# darwin-integrated.net
KiCad netlist of a schematic drawn in EAGLE
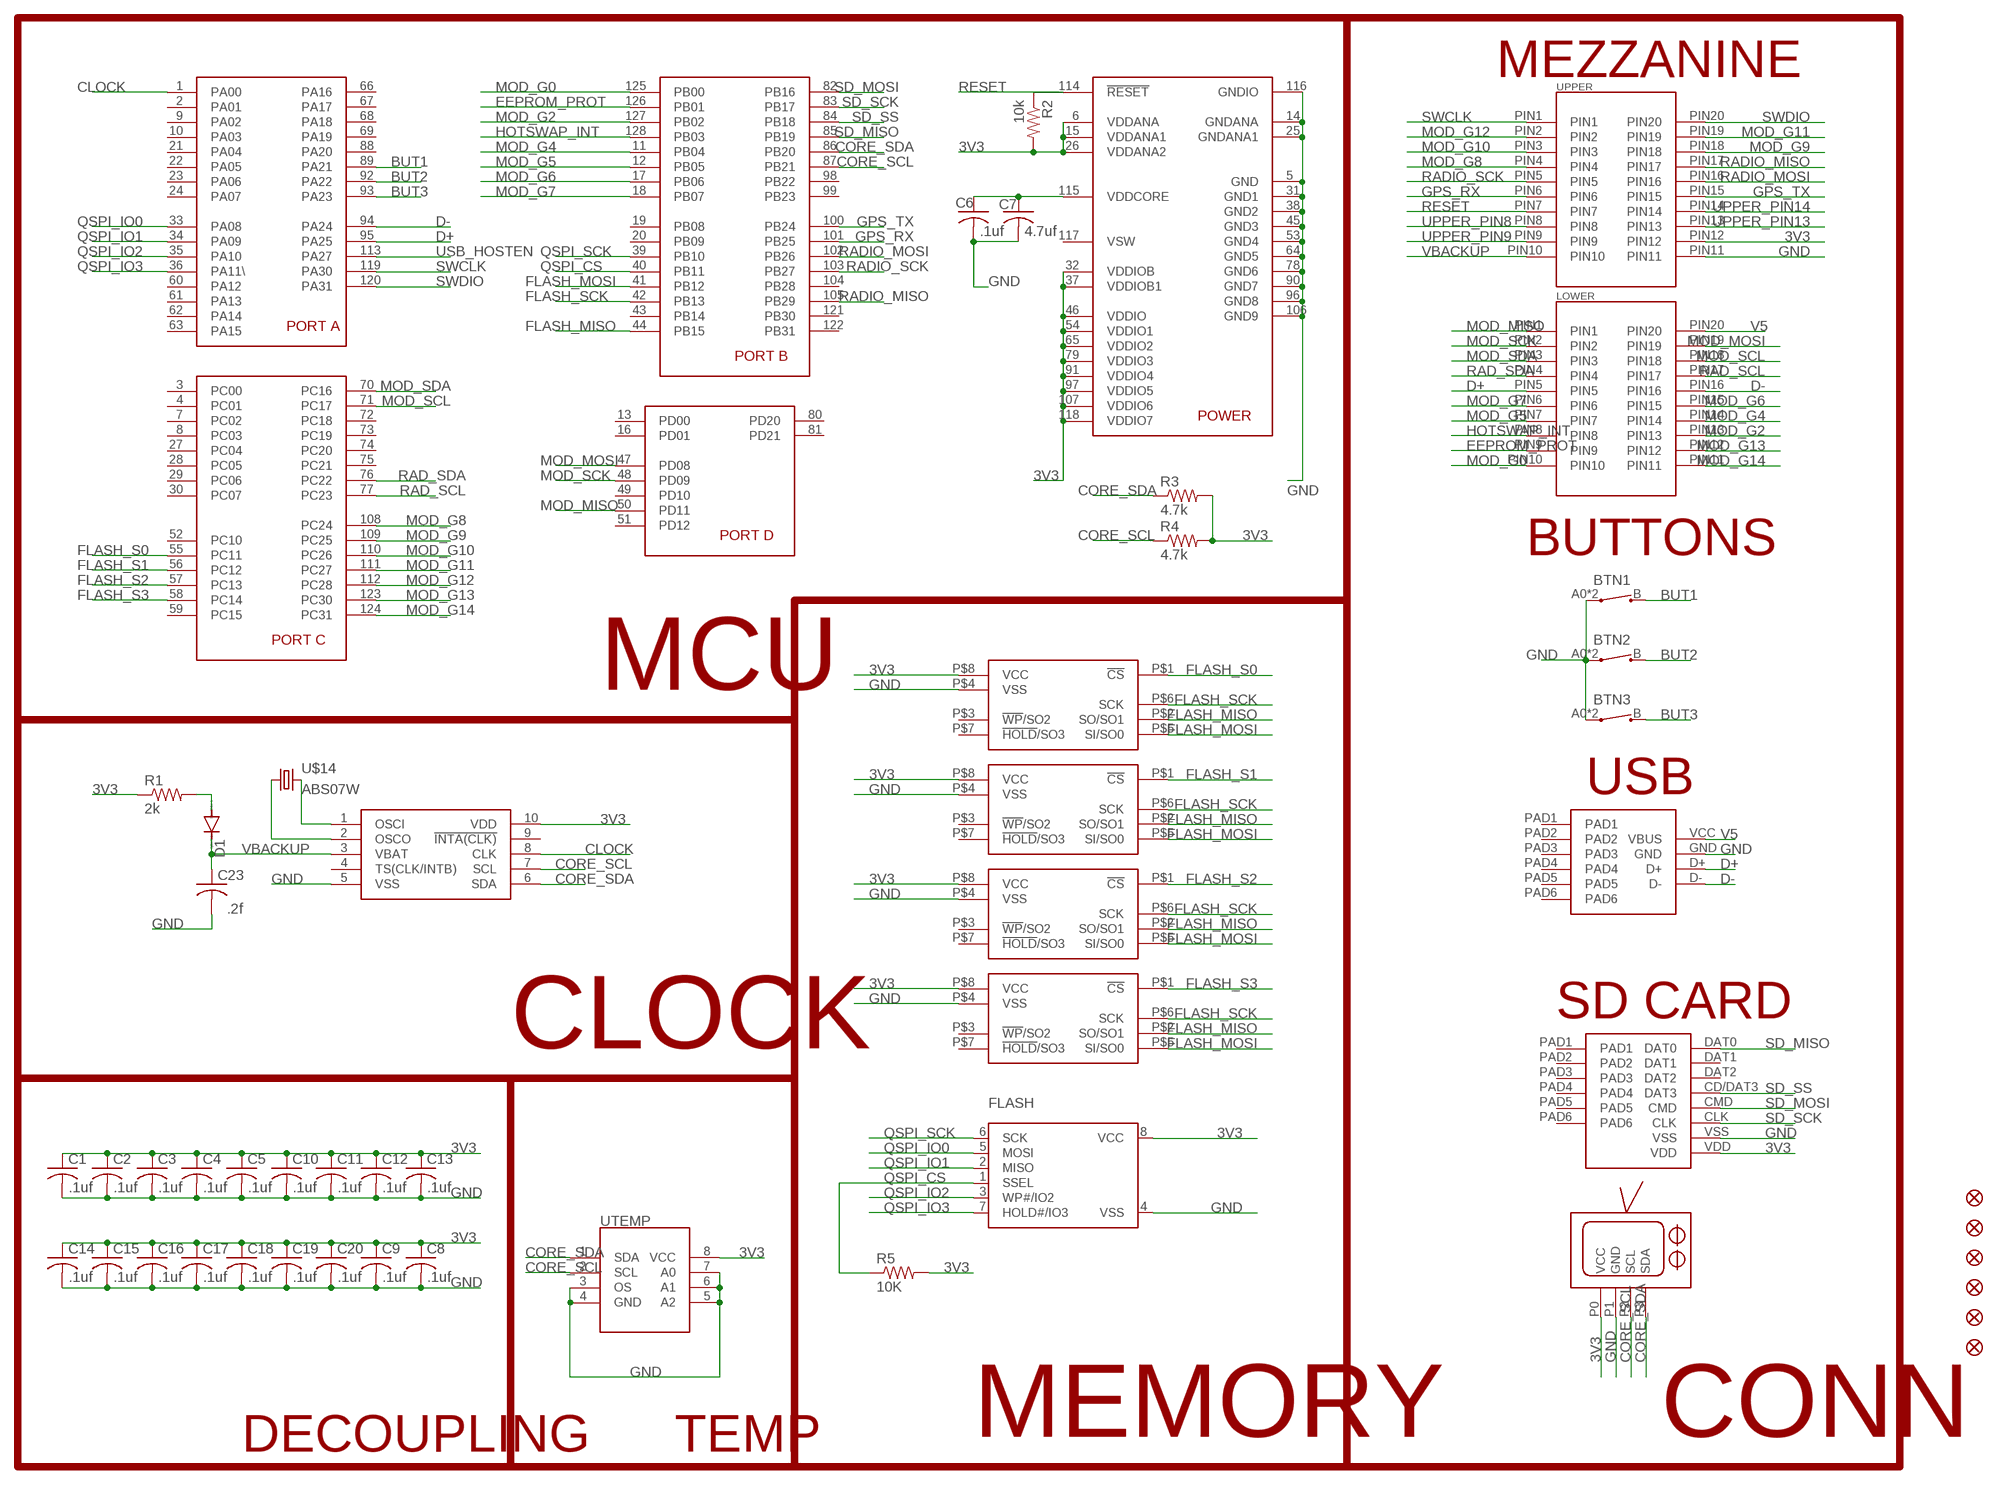
[diagram p0: schematic, sheet 1]

(export (version "E")
  (design (tool "Eeschema 10.0.6"))
  (components
    (comp (ref "BRAIN")
      (value "SAMD51PXXA")
      (footprint "eagle-import:SQFP-S-14X14-128")
      (libsource (lib "eagle-import") (part "SAMD51PXXA"))
    )
    (comp (ref "BTN1")
      (value "EVP-AEJB2A")
      (footprint "eagle-import:EVP-AEJB2A")
      (libsource (lib "eagle-import") (part "EVP-AEJB2A"))
    )
    (comp (ref "BTN2")
      (value "EVP-AEJB2A")
      (footprint "eagle-import:EVP-AEJB2A")
      (libsource (lib "eagle-import") (part "EVP-AEJB2A"))
    )
    (comp (ref "BTN3")
      (value "EVP-AEJB2A")
      (footprint "eagle-import:EVP-AEJB2A")
      (libsource (lib "eagle-import") (part "EVP-AEJB2A"))
    )
    (comp (ref "C1")
      (value ".1uf")
      (footprint "eagle-import:C0603K")
      (libsource (lib "eagle-import") (part "C-USC0603K"))
    )
    (comp (ref "C2")
      (value ".1uf")
      (footprint "eagle-import:C0603K")
      (libsource (lib "eagle-import") (part "C-USC0603K"))
    )
    (comp (ref "C3")
      (value ".1uf")
      (footprint "eagle-import:C0603K")
      (libsource (lib "eagle-import") (part "C-USC0603K"))
    )
    (comp (ref "C4")
      (value ".1uf")
      (footprint "eagle-import:C0603K")
      (libsource (lib "eagle-import") (part "C-USC0603K"))
    )
    (comp (ref "C5")
      (value ".1uf")
      (footprint "eagle-import:C0603K")
      (libsource (lib "eagle-import") (part "C-USC0603K"))
    )
    (comp (ref "C6")
      (value ".1uf")
      (footprint "eagle-import:C0603K")
      (libsource (lib "eagle-import") (part "C-USC0603K"))
    )
    (comp (ref "C7")
      (value "4.7uf")
      (footprint "eagle-import:C0603K")
      (libsource (lib "eagle-import") (part "C-USC0603K"))
    )
    (comp (ref "C8")
      (value ".1uf")
      (footprint "eagle-import:C0603K")
      (libsource (lib "eagle-import") (part "C-USC0603K"))
    )
    (comp (ref "C9")
      (value ".1uf")
      (footprint "eagle-import:C0603K")
      (libsource (lib "eagle-import") (part "C-USC0603K"))
    )
    (comp (ref "C10")
      (value ".1uf")
      (footprint "eagle-import:C0603K")
      (libsource (lib "eagle-import") (part "C-USC0603K"))
    )
    (comp (ref "C11")
      (value ".1uf")
      (footprint "eagle-import:C0603K")
      (libsource (lib "eagle-import") (part "C-USC0603K"))
    )
    (comp (ref "C12")
      (value ".1uf")
      (footprint "eagle-import:C0603K")
      (libsource (lib "eagle-import") (part "C-USC0603K"))
    )
    (comp (ref "C13")
      (value ".1uf")
      (footprint "eagle-import:C0603K")
      (libsource (lib "eagle-import") (part "C-USC0603K"))
    )
    (comp (ref "C14")
      (value ".1uf")
      (footprint "eagle-import:C0603K")
      (libsource (lib "eagle-import") (part "C-USC0603K"))
    )
    (comp (ref "C15")
      (value ".1uf")
      (footprint "eagle-import:C0603K")
      (libsource (lib "eagle-import") (part "C-USC0603K"))
    )
    (comp (ref "C16")
      (value ".1uf")
      (footprint "eagle-import:C0603K")
      (libsource (lib "eagle-import") (part "C-USC0603K"))
    )
    (comp (ref "C17")
      (value ".1uf")
      (footprint "eagle-import:C0603K")
      (libsource (lib "eagle-import") (part "C-USC0603K"))
    )
    (comp (ref "C18")
      (value ".1uf")
      (footprint "eagle-import:C0603K")
      (libsource (lib "eagle-import") (part "C-USC0603K"))
    )
    (comp (ref "C19")
      (value ".1uf")
      (footprint "eagle-import:C0603K")
      (libsource (lib "eagle-import") (part "C-USC0603K"))
    )
    (comp (ref "C20")
      (value ".1uf")
      (footprint "eagle-import:C0603K")
      (libsource (lib "eagle-import") (part "C-USC0603K"))
    )
    (comp (ref "C23")
      (value ".2f")
      (footprint "eagle-import:SUPERCAP")
      (libsource (lib "eagle-import") (part "DSK-3R3H204T614-H2L"))
    )
    (comp (ref "D1")
      (value "VS-10BQ015HM3/5BT")
      (footprint "eagle-import:SMB")
      (libsource (lib "eagle-import") (part "DIODE-SMB"))
    )
    (comp (ref "FID1")
      (value "FIDUCIAL_1MM")
      (footprint "eagle-import:FIDUCIAL_1MM")
      (libsource (lib "eagle-import") (part "FIDUCIAL_1MM"))
    )
    (comp (ref "FID2")
      (value "FIDUCIAL_1MM")
      (footprint "eagle-import:FIDUCIAL_1MM")
      (libsource (lib "eagle-import") (part "FIDUCIAL_1MM"))
    )
    (comp (ref "FID3")
      (value "FIDUCIAL_1MM")
      (footprint "eagle-import:FIDUCIAL_1MM")
      (libsource (lib "eagle-import") (part "FIDUCIAL_1MM"))
    )
    (comp (ref "FID4")
      (value "FIDUCIAL_1MM")
      (footprint "eagle-import:FIDUCIAL_1MM")
      (libsource (lib "eagle-import") (part "FIDUCIAL_1MM"))
    )
    (comp (ref "FID5")
      (value "FIDUCIAL_1MM")
      (footprint "eagle-import:FIDUCIAL_1MM")
      (libsource (lib "eagle-import") (part "FIDUCIAL_1MM"))
    )
    (comp (ref "FID6")
      (value "FIDUCIAL_1MM")
      (footprint "eagle-import:FIDUCIAL_1MM")
      (libsource (lib "eagle-import") (part "FIDUCIAL_1MM"))
    )
    (comp (ref "FLASH")
      (value "SPIFLASH_SOIC8208MIL")
      (footprint "eagle-import:SOIC8_208MIL")
      (libsource (lib "eagle-import") (part "SPIFLASH_SOIC8208MIL"))
    )
    (comp (ref "LOWER")
      (value "MOLEX-15-91-2200F")
      (footprint "eagle-import:20PH-F")
      (libsource (lib "eagle-import") (part "MOLEX-15-91-2200F"))
    )
    (comp (ref "R1")
      (value "2k")
      (footprint "eagle-import:R0603")
      (libsource (lib "eagle-import") (part "R-US_R0603"))
    )
    (comp (ref "R2")
      (value "10k")
      (footprint "eagle-import:R0603")
      (libsource (lib "eagle-import") (part "R-US_R0603"))
    )
    (comp (ref "R3")
      (value "4.7k")
      (footprint "eagle-import:R0603")
      (libsource (lib "eagle-import") (part "R-US_R0603"))
    )
    (comp (ref "R4")
      (value "4.7k")
      (footprint "eagle-import:R0603")
      (libsource (lib "eagle-import") (part "R-US_R0603"))
    )
    (comp (ref "R5")
      (value "10K")
      (footprint "eagle-import:R0603")
      (libsource (lib "eagle-import") (part "R-US_R0603"))
    )
    (comp (ref "RTC")
      (value "PCF85363ATT")
      (footprint "eagle-import:SOP50P490X110-10")
      (libsource (lib "eagle-import") (part "PCF85363ATT"))
    )
    (comp (ref "SCREEN")
      (value "SCREEN")
      (footprint "eagle-import:SCREEN")
      (libsource (lib "eagle-import") (part "SCREEN"))
    )
    (comp (ref "SD")
      (value "DM3D-SF")
      (footprint "eagle-import:DM3D-SF")
      (libsource (lib "eagle-import") (part "DM3D-SF"))
    )
    (comp (ref "U$14")
      (value "ABS07W")
      (footprint "eagle-import:ABS07W")
      (libsource (lib "eagle-import") (part "ABS07W"))
    )
    (comp (ref "U1")
      (value "TC58CVG1S3HRAIG")
      (footprint "eagle-import:WSON8")
      (libsource (lib "eagle-import") (part "TC58CVG1S3HRAIG"))
    )
    (comp (ref "U2")
      (value "TC58CVG1S3HRAIG")
      (footprint "eagle-import:WSON8")
      (libsource (lib "eagle-import") (part "TC58CVG1S3HRAIG"))
    )
    (comp (ref "U3")
      (value "TC58CVG1S3HRAIG")
      (footprint "eagle-import:WSON8")
      (libsource (lib "eagle-import") (part "TC58CVG1S3HRAIG"))
    )
    (comp (ref "U4")
      (value "TC58CVG1S3HRAIG")
      (footprint "eagle-import:WSON8")
      (libsource (lib "eagle-import") (part "TC58CVG1S3HRAIG"))
    )
    (comp (ref "UPPER")
      (value "MOLEX-15-91-2200F")
      (footprint "eagle-import:20PH-F")
      (libsource (lib "eagle-import") (part "MOLEX-15-91-2200F"))
    )
    (comp (ref "USB")
      (value "MOLEX-47491-0001")
      (footprint "eagle-import:MOELX-47491-0001")
      (libsource (lib "eagle-import") (part "MOLEX-47491-0001"))
    )
    (comp (ref "UTEMP")
      (value "PCT2075")
      (footprint "eagle-import:SO8")
      (libsource (lib "eagle-import") (part "PCT2075"))
    )
  )
  (nets
    (net (code "1") (name "/3V3") (class "Default")
      (node (ref "BRAIN") (pin "107") (pinfunction "VDDIO6_107") (pintype "bidirectional"))
      (node (ref "BRAIN") (pin "118") (pinfunction "VDDIO7_118") (pintype "bidirectional"))
      (node (ref "BRAIN") (pin "15") (pinfunction "VDDANA1_15") (pintype "bidirectional"))
      (node (ref "BRAIN") (pin "26") (pinfunction "VDDANA2_26") (pintype "bidirectional"))
      (node (ref "BRAIN") (pin "32") (pinfunction "VDDIOB_32") (pintype "bidirectional"))
      (node (ref "BRAIN") (pin "37") (pinfunction "VDDIOB1_37") (pintype "bidirectional"))
      (node (ref "BRAIN") (pin "46") (pinfunction "VDDIO_46") (pintype "bidirectional"))
      (node (ref "BRAIN") (pin "54") (pinfunction "VDDIO1_54") (pintype "bidirectional"))
      (node (ref "BRAIN") (pin "6") (pinfunction "VDDANA_6") (pintype "bidirectional"))
      (node (ref "BRAIN") (pin "65") (pinfunction "VDDIO2_65") (pintype "bidirectional"))
      (node (ref "BRAIN") (pin "79") (pinfunction "VDDIO3_79") (pintype "bidirectional"))
      (node (ref "BRAIN") (pin "91") (pinfunction "VDDIO4_91") (pintype "bidirectional"))
      (node (ref "BRAIN") (pin "97") (pinfunction "VDDIO5_97") (pintype "bidirectional"))
      (node (ref "C1") (pin "1") (pinfunction "1_1") (pintype "passive"))
      (node (ref "C10") (pin "1") (pinfunction "1_1") (pintype "passive"))
      (node (ref "C11") (pin "1") (pinfunction "1_1") (pintype "passive"))
      (node (ref "C12") (pin "1") (pinfunction "1_1") (pintype "passive"))
      (node (ref "C13") (pin "1") (pinfunction "1_1") (pintype "passive"))
      (node (ref "C14") (pin "1") (pinfunction "1_1") (pintype "passive"))
      (node (ref "C15") (pin "1") (pinfunction "1_1") (pintype "passive"))
      (node (ref "C16") (pin "1") (pinfunction "1_1") (pintype "passive"))
      (node (ref "C17") (pin "1") (pinfunction "1_1") (pintype "passive"))
      (node (ref "C18") (pin "1") (pinfunction "1_1") (pintype "passive"))
      (node (ref "C19") (pin "1") (pinfunction "1_1") (pintype "passive"))
      (node (ref "C2") (pin "1") (pinfunction "1_1") (pintype "passive"))
      (node (ref "C20") (pin "1") (pinfunction "1_1") (pintype "passive"))
      (node (ref "C3") (pin "1") (pinfunction "1_1") (pintype "passive"))
      (node (ref "C4") (pin "1") (pinfunction "1_1") (pintype "passive"))
      (node (ref "C5") (pin "1") (pinfunction "1_1") (pintype "passive"))
      (node (ref "C8") (pin "1") (pinfunction "1_1") (pintype "passive"))
      (node (ref "C9") (pin "1") (pinfunction "1_1") (pintype "passive"))
      (node (ref "FLASH") (pin "8") (pinfunction "VCC_8") (pintype "bidirectional"))
      (node (ref "R1") (pin "1") (pinfunction "1_1") (pintype "passive"))
      (node (ref "R2") (pin "2") (pinfunction "2_2") (pintype "passive"))
      (node (ref "R3") (pin "2") (pinfunction "2_2") (pintype "passive"))
      (node (ref "R4") (pin "2") (pinfunction "2_2") (pintype "passive"))
      (node (ref "R5") (pin "2") (pinfunction "2_2") (pintype "passive"))
      (node (ref "RTC") (pin "10") (pinfunction "VDD_10") (pintype "bidirectional"))
      (node (ref "SCREEN") (pin "P0") (pinfunction "VCC_P0") (pintype "bidirectional"))
      (node (ref "SD") (pin "VDD") (pinfunction "VDD_VDD") (pintype "bidirectional"))
      (node (ref "U1") (pin "P$8") (pinfunction "VCC_P$8") (pintype "bidirectional"))
      (node (ref "U2") (pin "P$8") (pinfunction "VCC_P$8") (pintype "bidirectional"))
      (node (ref "U3") (pin "P$8") (pinfunction "VCC_P$8") (pintype "bidirectional"))
      (node (ref "U4") (pin "P$8") (pinfunction "VCC_P$8") (pintype "bidirectional"))
      (node (ref "UPPER") (pin "PIN12") (pinfunction "PIN12_PIN12") (pintype "bidirectional"))
      (node (ref "UTEMP") (pin "8") (pinfunction "VCC_8") (pintype "bidirectional"))
    )
    (net (code "2") (name "/BUT1") (class "Default")
      (node (ref "BRAIN") (pin "89") (pinfunction "PA21_89") (pintype "bidirectional"))
      (node (ref "BTN1") (pin "B") (pinfunction "2_B") (pintype "passive"))
    )
    (net (code "3") (name "/BUT2") (class "Default")
      (node (ref "BRAIN") (pin "92") (pinfunction "PA22_92") (pintype "bidirectional"))
      (node (ref "BTN2") (pin "B") (pinfunction "2_B") (pintype "passive"))
    )
    (net (code "4") (name "/BUT3") (class "Default")
      (node (ref "BRAIN") (pin "93") (pinfunction "PA23_93") (pintype "bidirectional"))
      (node (ref "BTN3") (pin "B") (pinfunction "2_B") (pintype "passive"))
    )
    (net (code "5") (name "/CLOCK") (class "Default")
      (node (ref "BRAIN") (pin "1") (pinfunction "PA00_1") (pintype "bidirectional"))
      (node (ref "RTC") (pin "8") (pinfunction "CLK_8") (pintype "bidirectional"))
    )
    (net (code "6") (name "/CORE_SCL") (class "Default")
      (node (ref "BRAIN") (pin "87") (pinfunction "PB21_87") (pintype "bidirectional"))
      (node (ref "R4") (pin "1") (pinfunction "1_1") (pintype "passive"))
      (node (ref "RTC") (pin "7") (pinfunction "SCL_7") (pintype "bidirectional"))
      (node (ref "SCREEN") (pin "P2") (pinfunction "SCL_P2") (pintype "bidirectional"))
      (node (ref "UTEMP") (pin "2") (pinfunction "SCL_2") (pintype "bidirectional"))
    )
    (net (code "7") (name "/CORE_SDA") (class "Default")
      (node (ref "BRAIN") (pin "86") (pinfunction "PB20_86") (pintype "bidirectional"))
      (node (ref "R3") (pin "1") (pinfunction "1_1") (pintype "passive"))
      (node (ref "RTC") (pin "6") (pinfunction "SDA_6") (pintype "bidirectional"))
      (node (ref "SCREEN") (pin "P3") (pinfunction "SDA_P3") (pintype "bidirectional"))
      (node (ref "UTEMP") (pin "1") (pinfunction "SDA_1") (pintype "bidirectional"))
    )
    (net (code "8") (name "/D+") (class "Default")
      (node (ref "BRAIN") (pin "95") (pinfunction "PA25_95") (pintype "bidirectional"))
      (node (ref "LOWER") (pin "PIN5") (pinfunction "PIN5_PIN5") (pintype "bidirectional"))
      (node (ref "USB") (pin "D+") (pinfunction "D+_D+") (pintype "bidirectional"))
    )
    (net (code "9") (name "/D-") (class "Default")
      (node (ref "BRAIN") (pin "94") (pinfunction "PA24_94") (pintype "bidirectional"))
      (node (ref "LOWER") (pin "PIN16") (pinfunction "PIN16_PIN16") (pintype "bidirectional"))
      (node (ref "USB") (pin "D-") (pinfunction "D-_D-") (pintype "bidirectional"))
    )
    (net (code "10") (name "/EEPROM_PROT") (class "Default")
      (node (ref "BRAIN") (pin "126") (pinfunction "PB01_126") (pintype "bidirectional"))
      (node (ref "LOWER") (pin "PIN9") (pinfunction "PIN9_PIN9") (pintype "bidirectional"))
    )
    (net (code "11") (name "/FLASH_MISO") (class "Default")
      (node (ref "BRAIN") (pin "44") (pinfunction "PB15_44") (pintype "bidirectional"))
      (node (ref "U1") (pin "P$2") (pinfunction "SO/SO1_P$2") (pintype "bidirectional"))
      (node (ref "U2") (pin "P$2") (pinfunction "SO/SO1_P$2") (pintype "bidirectional"))
      (node (ref "U3") (pin "P$2") (pinfunction "SO/SO1_P$2") (pintype "bidirectional"))
      (node (ref "U4") (pin "P$2") (pinfunction "SO/SO1_P$2") (pintype "bidirectional"))
    )
    (net (code "12") (name "/FLASH_MOSI") (class "Default")
      (node (ref "BRAIN") (pin "41") (pinfunction "PB12_41") (pintype "bidirectional"))
      (node (ref "U1") (pin "P$5") (pinfunction "SI/SO0_P$5") (pintype "bidirectional"))
      (node (ref "U2") (pin "P$5") (pinfunction "SI/SO0_P$5") (pintype "bidirectional"))
      (node (ref "U3") (pin "P$5") (pinfunction "SI/SO0_P$5") (pintype "bidirectional"))
      (node (ref "U4") (pin "P$5") (pinfunction "SI/SO0_P$5") (pintype "bidirectional"))
    )
    (net (code "13") (name "/FLASH_S0") (class "Default")
      (node (ref "BRAIN") (pin "55") (pinfunction "PC11_55") (pintype "bidirectional"))
      (node (ref "U1") (pin "P$1") (pinfunction "~{CS}_P$1") (pintype "bidirectional"))
    )
    (net (code "14") (name "/FLASH_S1") (class "Default")
      (node (ref "BRAIN") (pin "56") (pinfunction "PC12_56") (pintype "bidirectional"))
      (node (ref "U2") (pin "P$1") (pinfunction "~{CS}_P$1") (pintype "bidirectional"))
    )
    (net (code "15") (name "/FLASH_S2") (class "Default")
      (node (ref "BRAIN") (pin "57") (pinfunction "PC13_57") (pintype "bidirectional"))
      (node (ref "U3") (pin "P$1") (pinfunction "~{CS}_P$1") (pintype "bidirectional"))
    )
    (net (code "16") (name "/FLASH_S3") (class "Default")
      (node (ref "BRAIN") (pin "58") (pinfunction "PC14_58") (pintype "bidirectional"))
      (node (ref "U4") (pin "P$1") (pinfunction "~{CS}_P$1") (pintype "bidirectional"))
    )
    (net (code "17") (name "/FLASH_SCK") (class "Default")
      (node (ref "BRAIN") (pin "42") (pinfunction "PB13_42") (pintype "bidirectional"))
      (node (ref "U1") (pin "P$6") (pinfunction "SCK_P$6") (pintype "bidirectional"))
      (node (ref "U2") (pin "P$6") (pinfunction "SCK_P$6") (pintype "bidirectional"))
      (node (ref "U3") (pin "P$6") (pinfunction "SCK_P$6") (pintype "bidirectional"))
      (node (ref "U4") (pin "P$6") (pinfunction "SCK_P$6") (pintype "bidirectional"))
    )
    (net (code "18") (name "/GND") (class "Default")
      (node (ref "BRAIN") (pin "106") (pinfunction "GND9_106") (pintype "bidirectional"))
      (node (ref "BRAIN") (pin "116") (pinfunction "GNDIO_116") (pintype "bidirectional"))
      (node (ref "BRAIN") (pin "14") (pinfunction "GNDANA_14") (pintype "bidirectional"))
      (node (ref "BRAIN") (pin "25") (pinfunction "GNDANA1_25") (pintype "bidirectional"))
      (node (ref "BRAIN") (pin "31") (pinfunction "GND1_31") (pintype "bidirectional"))
      (node (ref "BRAIN") (pin "38") (pinfunction "GND2_38") (pintype "bidirectional"))
      (node (ref "BRAIN") (pin "45") (pinfunction "GND3_45") (pintype "bidirectional"))
      (node (ref "BRAIN") (pin "5") (pinfunction "GND_5") (pintype "bidirectional"))
      (node (ref "BRAIN") (pin "53") (pinfunction "GND4_53") (pintype "bidirectional"))
      (node (ref "BRAIN") (pin "64") (pinfunction "GND5_64") (pintype "bidirectional"))
      (node (ref "BRAIN") (pin "78") (pinfunction "GND6_78") (pintype "bidirectional"))
      (node (ref "BRAIN") (pin "90") (pinfunction "GND7_90") (pintype "bidirectional"))
      (node (ref "BRAIN") (pin "96") (pinfunction "GND8_96") (pintype "bidirectional"))
      (node (ref "BTN1") (pin "A0") (pinfunction "1_A0") (pintype "passive"))
      (node (ref "BTN1") (pin "A1") (pinfunction "1_A1") (pintype "passive"))
      (node (ref "BTN2") (pin "A0") (pinfunction "1_A0") (pintype "passive"))
      (node (ref "BTN2") (pin "A1") (pinfunction "1_A1") (pintype "passive"))
      (node (ref "BTN3") (pin "A0") (pinfunction "1_A0") (pintype "passive"))
      (node (ref "BTN3") (pin "A1") (pinfunction "1_A1") (pintype "passive"))
      (node (ref "C1") (pin "2") (pinfunction "2_2") (pintype "passive"))
      (node (ref "C10") (pin "2") (pinfunction "2_2") (pintype "passive"))
      (node (ref "C11") (pin "2") (pinfunction "2_2") (pintype "passive"))
      (node (ref "C12") (pin "2") (pinfunction "2_2") (pintype "passive"))
      (node (ref "C13") (pin "2") (pinfunction "2_2") (pintype "passive"))
      (node (ref "C14") (pin "2") (pinfunction "2_2") (pintype "passive"))
      (node (ref "C15") (pin "2") (pinfunction "2_2") (pintype "passive"))
      (node (ref "C16") (pin "2") (pinfunction "2_2") (pintype "passive"))
      (node (ref "C17") (pin "2") (pinfunction "2_2") (pintype "passive"))
      (node (ref "C18") (pin "2") (pinfunction "2_2") (pintype "passive"))
      (node (ref "C19") (pin "2") (pinfunction "2_2") (pintype "passive"))
      (node (ref "C2") (pin "2") (pinfunction "2_2") (pintype "passive"))
      (node (ref "C20") (pin "2") (pinfunction "2_2") (pintype "passive"))
      (node (ref "C23") (pin "-") (pinfunction "-_-") (pintype "passive"))
      (node (ref "C3") (pin "2") (pinfunction "2_2") (pintype "passive"))
      (node (ref "C4") (pin "2") (pinfunction "2_2") (pintype "passive"))
      (node (ref "C5") (pin "2") (pinfunction "2_2") (pintype "passive"))
      (node (ref "C6") (pin "2") (pinfunction "2_2") (pintype "passive"))
      (node (ref "C7") (pin "2") (pinfunction "2_2") (pintype "passive"))
      (node (ref "C8") (pin "2") (pinfunction "2_2") (pintype "passive"))
      (node (ref "C9") (pin "2") (pinfunction "2_2") (pintype "passive"))
      (node (ref "FLASH") (pin "4") (pinfunction "VSS_4") (pintype "bidirectional"))
      (node (ref "RTC") (pin "5") (pinfunction "VSS_5") (pintype "bidirectional"))
      (node (ref "SCREEN") (pin "P1") (pinfunction "GND_P1") (pintype "bidirectional"))
      (node (ref "SD") (pin "VSS") (pinfunction "VSS_VSS") (pintype "bidirectional"))
      (node (ref "U1") (pin "P$4") (pinfunction "VSS_P$4") (pintype "bidirectional"))
      (node (ref "U2") (pin "P$4") (pinfunction "VSS_P$4") (pintype "bidirectional"))
      (node (ref "U3") (pin "P$4") (pinfunction "VSS_P$4") (pintype "bidirectional"))
      (node (ref "U4") (pin "P$4") (pinfunction "VSS_P$4") (pintype "bidirectional"))
      (node (ref "UPPER") (pin "PIN11") (pinfunction "PIN11_PIN11") (pintype "bidirectional"))
      (node (ref "USB") (pin "GND") (pinfunction "GND_GND") (pintype "bidirectional"))
      (node (ref "UTEMP") (pin "3") (pinfunction "OS_3") (pintype "bidirectional"))
      (node (ref "UTEMP") (pin "4") (pinfunction "GND_4") (pintype "bidirectional"))
      (node (ref "UTEMP") (pin "5") (pinfunction "A2_5") (pintype "bidirectional"))
      (node (ref "UTEMP") (pin "6") (pinfunction "A1_6") (pintype "bidirectional"))
      (node (ref "UTEMP") (pin "7") (pinfunction "A0_7") (pintype "bidirectional"))
    )
    (net (code "19") (name "/GPS_RX") (class "Default")
      (node (ref "BRAIN") (pin "101") (pinfunction "PB25_101") (pintype "bidirectional"))
      (node (ref "UPPER") (pin "PIN6") (pinfunction "PIN6_PIN6") (pintype "bidirectional"))
    )
    (net (code "20") (name "/GPS_TX") (class "Default")
      (node (ref "BRAIN") (pin "100") (pinfunction "PB24_100") (pintype "bidirectional"))
      (node (ref "UPPER") (pin "PIN15") (pinfunction "PIN15_PIN15") (pintype "bidirectional"))
    )
    (net (code "21") (name "/HOTSWAP_INT") (class "Default")
      (node (ref "BRAIN") (pin "128") (pinfunction "PB03_128") (pintype "bidirectional"))
      (node (ref "LOWER") (pin "PIN8") (pinfunction "PIN8_PIN8") (pintype "bidirectional"))
    )
    (net (code "22") (name "/MOD_G0") (class "Default")
      (node (ref "BRAIN") (pin "125") (pinfunction "PB00_125") (pintype "bidirectional"))
      (node (ref "LOWER") (pin "PIN10") (pinfunction "PIN10_PIN10") (pintype "bidirectional"))
    )
    (net (code "23") (name "/MOD_G2") (class "Default")
      (node (ref "BRAIN") (pin "127") (pinfunction "PB02_127") (pintype "bidirectional"))
      (node (ref "LOWER") (pin "PIN13") (pinfunction "PIN13_PIN13") (pintype "bidirectional"))
    )
    (net (code "24") (name "/MOD_G4") (class "Default")
      (node (ref "BRAIN") (pin "11") (pinfunction "PB04_11") (pintype "bidirectional"))
      (node (ref "LOWER") (pin "PIN14") (pinfunction "PIN14_PIN14") (pintype "bidirectional"))
    )
    (net (code "25") (name "/MOD_G5") (class "Default")
      (node (ref "BRAIN") (pin "12") (pinfunction "PB05_12") (pintype "bidirectional"))
      (node (ref "LOWER") (pin "PIN7") (pinfunction "PIN7_PIN7") (pintype "bidirectional"))
    )
    (net (code "26") (name "/MOD_G6") (class "Default")
      (node (ref "BRAIN") (pin "17") (pinfunction "PB06_17") (pintype "bidirectional"))
      (node (ref "LOWER") (pin "PIN15") (pinfunction "PIN15_PIN15") (pintype "bidirectional"))
    )
    (net (code "27") (name "/MOD_G7") (class "Default")
      (node (ref "BRAIN") (pin "18") (pinfunction "PB07_18") (pintype "bidirectional"))
      (node (ref "LOWER") (pin "PIN6") (pinfunction "PIN6_PIN6") (pintype "bidirectional"))
    )
    (net (code "28") (name "/MOD_G8") (class "Default")
      (node (ref "BRAIN") (pin "108") (pinfunction "PC24_108") (pintype "bidirectional"))
      (node (ref "UPPER") (pin "PIN4") (pinfunction "PIN4_PIN4") (pintype "bidirectional"))
    )
    (net (code "29") (name "/MOD_G9") (class "Default")
      (node (ref "BRAIN") (pin "109") (pinfunction "PC25_109") (pintype "bidirectional"))
      (node (ref "UPPER") (pin "PIN18") (pinfunction "PIN18_PIN18") (pintype "bidirectional"))
    )
    (net (code "30") (name "/MOD_G10") (class "Default")
      (node (ref "BRAIN") (pin "110") (pinfunction "PC26_110") (pintype "bidirectional"))
      (node (ref "UPPER") (pin "PIN3") (pinfunction "PIN3_PIN3") (pintype "bidirectional"))
    )
    (net (code "31") (name "/MOD_G11") (class "Default")
      (node (ref "BRAIN") (pin "111") (pinfunction "PC27_111") (pintype "bidirectional"))
      (node (ref "UPPER") (pin "PIN19") (pinfunction "PIN19_PIN19") (pintype "bidirectional"))
    )
    (net (code "32") (name "/MOD_G12") (class "Default")
      (node (ref "BRAIN") (pin "112") (pinfunction "PC28_112") (pintype "bidirectional"))
      (node (ref "UPPER") (pin "PIN2") (pinfunction "PIN2_PIN2") (pintype "bidirectional"))
    )
    (net (code "33") (name "/MOD_G13") (class "Default")
      (node (ref "BRAIN") (pin "123") (pinfunction "PC30_123") (pintype "bidirectional"))
      (node (ref "LOWER") (pin "PIN12") (pinfunction "PIN12_PIN12") (pintype "bidirectional"))
    )
    (net (code "34") (name "/MOD_G14") (class "Default")
      (node (ref "BRAIN") (pin "124") (pinfunction "PC31_124") (pintype "bidirectional"))
      (node (ref "LOWER") (pin "PIN11") (pinfunction "PIN11_PIN11") (pintype "bidirectional"))
    )
    (net (code "35") (name "/MOD_MISO") (class "Default")
      (node (ref "BRAIN") (pin "50") (pinfunction "PD11_50") (pintype "bidirectional"))
      (node (ref "LOWER") (pin "PIN1") (pinfunction "PIN1_PIN1") (pintype "bidirectional"))
    )
    (net (code "36") (name "/MOD_MOSI") (class "Default")
      (node (ref "BRAIN") (pin "47") (pinfunction "PD08_47") (pintype "bidirectional"))
      (node (ref "LOWER") (pin "PIN19") (pinfunction "PIN19_PIN19") (pintype "bidirectional"))
    )
    (net (code "37") (name "/MOD_SCK") (class "Default")
      (node (ref "BRAIN") (pin "48") (pinfunction "PD09_48") (pintype "bidirectional"))
      (node (ref "LOWER") (pin "PIN2") (pinfunction "PIN2_PIN2") (pintype "bidirectional"))
    )
    (net (code "38") (name "/MOD_SCL") (class "Default")
      (node (ref "BRAIN") (pin "71") (pinfunction "PC17_71") (pintype "bidirectional"))
      (node (ref "LOWER") (pin "PIN18") (pinfunction "PIN18_PIN18") (pintype "bidirectional"))
    )
    (net (code "39") (name "/MOD_SDA") (class "Default")
      (node (ref "BRAIN") (pin "70") (pinfunction "PC16_70") (pintype "bidirectional"))
      (node (ref "LOWER") (pin "PIN3") (pinfunction "PIN3_PIN3") (pintype "bidirectional"))
    )
    (net (code "40") (name "/QSPI_CS") (class "Default")
      (node (ref "BRAIN") (pin "40") (pinfunction "PB11_40") (pintype "bidirectional"))
      (node (ref "FLASH") (pin "1") (pinfunction "SSEL_1") (pintype "bidirectional"))
      (node (ref "R5") (pin "1") (pinfunction "1_1") (pintype "passive"))
    )
    (net (code "41") (name "/QSPI_IO0") (class "Default")
      (node (ref "BRAIN") (pin "33") (pinfunction "PA08_33") (pintype "bidirectional"))
      (node (ref "FLASH") (pin "5") (pinfunction "MOSI_5") (pintype "bidirectional"))
    )
    (net (code "42") (name "/QSPI_IO1") (class "Default")
      (node (ref "BRAIN") (pin "34") (pinfunction "PA09_34") (pintype "bidirectional"))
      (node (ref "FLASH") (pin "2") (pinfunction "MISO_2") (pintype "bidirectional"))
    )
    (net (code "43") (name "/QSPI_IO2") (class "Default")
      (node (ref "BRAIN") (pin "35") (pinfunction "PA10_35") (pintype "bidirectional"))
      (node (ref "FLASH") (pin "3") (pinfunction "WP#/IO2_3") (pintype "bidirectional"))
    )
    (net (code "44") (name "/QSPI_IO3") (class "Default")
      (node (ref "BRAIN") (pin "36") (pinfunction "PA11\\_36") (pintype "bidirectional"))
      (node (ref "FLASH") (pin "7") (pinfunction "HOLD#/IO3_7") (pintype "bidirectional"))
    )
    (net (code "45") (name "/QSPI_SCK") (class "Default")
      (node (ref "BRAIN") (pin "39") (pinfunction "PB10_39") (pintype "bidirectional"))
      (node (ref "FLASH") (pin "6") (pinfunction "SCK_6") (pintype "bidirectional"))
    )
    (net (code "46") (name "/RADIO_MISO") (class "Default")
      (node (ref "BRAIN") (pin "105") (pinfunction "PB29_105") (pintype "bidirectional"))
      (node (ref "UPPER") (pin "PIN17") (pinfunction "PIN17_PIN17") (pintype "bidirectional"))
    )
    (net (code "47") (name "/RADIO_MOSI") (class "Default")
      (node (ref "BRAIN") (pin "102") (pinfunction "PB26_102") (pintype "bidirectional"))
      (node (ref "UPPER") (pin "PIN16") (pinfunction "PIN16_PIN16") (pintype "bidirectional"))
    )
    (net (code "48") (name "/RADIO_SCK") (class "Default")
      (node (ref "BRAIN") (pin "103") (pinfunction "PB27_103") (pintype "bidirectional"))
      (node (ref "UPPER") (pin "PIN5") (pinfunction "PIN5_PIN5") (pintype "bidirectional"))
    )
    (net (code "49") (name "/RAD_SCL") (class "Default")
      (node (ref "BRAIN") (pin "77") (pinfunction "PC23_77") (pintype "bidirectional"))
      (node (ref "LOWER") (pin "PIN17") (pinfunction "PIN17_PIN17") (pintype "bidirectional"))
    )
    (net (code "50") (name "/RAD_SDA") (class "Default")
      (node (ref "BRAIN") (pin "76") (pinfunction "PC22_76") (pintype "bidirectional"))
      (node (ref "LOWER") (pin "PIN4") (pinfunction "PIN4_PIN4") (pintype "bidirectional"))
    )
    (net (code "51") (name "/RESET") (class "Default")
      (node (ref "BRAIN") (pin "114") (pinfunction "~{RESET}_114") (pintype "bidirectional"))
      (node (ref "R2") (pin "1") (pinfunction "1_1") (pintype "passive"))
      (node (ref "UPPER") (pin "PIN7") (pinfunction "PIN7_PIN7") (pintype "bidirectional"))
    )
    (net (code "52") (name "/SD_MISO") (class "Default")
      (node (ref "BRAIN") (pin "85") (pinfunction "PB19_85") (pintype "bidirectional"))
      (node (ref "SD") (pin "DAT0") (pinfunction "DAT0_DAT0") (pintype "bidirectional"))
    )
    (net (code "53") (name "/SD_MOSI") (class "Default")
      (node (ref "BRAIN") (pin "82") (pinfunction "PB16_82") (pintype "bidirectional"))
      (node (ref "SD") (pin "CMD") (pinfunction "CMD_CMD") (pintype "bidirectional"))
    )
    (net (code "54") (name "/SD_SCK") (class "Default")
      (node (ref "BRAIN") (pin "83") (pinfunction "PB17_83") (pintype "bidirectional"))
      (node (ref "SD") (pin "CLK") (pinfunction "CLK_CLK") (pintype "bidirectional"))
    )
    (net (code "55") (name "/SD_SS") (class "Default")
      (node (ref "BRAIN") (pin "84") (pinfunction "PB18_84") (pintype "bidirectional"))
      (node (ref "SD") (pin "CD/DAT3") (pinfunction "DAT3_CD/DAT3") (pintype "bidirectional"))
    )
    (net (code "56") (name "/SWCLK") (class "Default")
      (node (ref "BRAIN") (pin "119") (pinfunction "PA30_119") (pintype "bidirectional"))
      (node (ref "UPPER") (pin "PIN1") (pinfunction "PIN1_PIN1") (pintype "bidirectional"))
    )
    (net (code "57") (name "/SWDIO") (class "Default")
      (node (ref "BRAIN") (pin "120") (pinfunction "PA31_120") (pintype "bidirectional"))
      (node (ref "UPPER") (pin "PIN20") (pinfunction "PIN20_PIN20") (pintype "bidirectional"))
    )
    (net (code "58") (name "/UPPER_PIN8") (class "Default")
      (node (ref "UPPER") (pin "PIN8") (pinfunction "PIN8_PIN8") (pintype "bidirectional"))
    )
    (net (code "59") (name "/UPPER_PIN9") (class "Default")
      (node (ref "UPPER") (pin "PIN9") (pinfunction "PIN9_PIN9") (pintype "bidirectional"))
    )
    (net (code "60") (name "/UPPER_PIN13") (class "Default")
      (node (ref "UPPER") (pin "PIN13") (pinfunction "PIN13_PIN13") (pintype "bidirectional"))
    )
    (net (code "61") (name "/UPPER_PIN14") (class "Default")
      (node (ref "UPPER") (pin "PIN14") (pinfunction "PIN14_PIN14") (pintype "bidirectional"))
    )
    (net (code "62") (name "/USB_HOSTEN") (class "Default")
      (node (ref "BRAIN") (pin "113") (pinfunction "PA27_113") (pintype "bidirectional"))
    )
    (net (code "63") (name "/V5") (class "Default")
      (node (ref "LOWER") (pin "PIN20") (pinfunction "PIN20_PIN20") (pintype "bidirectional"))
      (node (ref "USB") (pin "VCC") (pinfunction "VBUS_VCC") (pintype "bidirectional"))
    )
    (net (code "64") (name "/VBACKUP") (class "Default")
      (node (ref "C23") (pin "+") (pinfunction "+_+") (pintype "passive"))
      (node (ref "D1") (pin "C") (pinfunction "C_C") (pintype "passive"))
      (node (ref "RTC") (pin "3") (pinfunction "VBAT_3") (pintype "bidirectional"))
      (node (ref "UPPER") (pin "PIN10") (pinfunction "PIN10_PIN10") (pintype "bidirectional"))
    )
    (net (code "65") (name "Net-(BRAINE-VDDCORE)") (class "Default")
      (node (ref "BRAIN") (pin "115") (pinfunction "VDDCORE_115") (pintype "bidirectional"))
      (node (ref "C6") (pin "1") (pinfunction "1_1") (pintype "passive"))
      (node (ref "C7") (pin "1") (pinfunction "1_1") (pintype "passive"))
    )
    (net (code "66") (name "Net-(D1-PadA)") (class "Default")
      (node (ref "D1") (pin "A") (pinfunction "A_A") (pintype "passive"))
      (node (ref "R1") (pin "2") (pinfunction "2_2") (pintype "passive"))
    )
    (net (code "67") (name "Net-(RTC-OSCI)") (class "Default")
      (node (ref "RTC") (pin "1") (pinfunction "OSCI_1") (pintype "bidirectional"))
      (node (ref "U$14") (pin "P$2") (pinfunction "2_P$2") (pintype "passive"))
    )
    (net (code "68") (name "Net-(RTC-OSCO)") (class "Default")
      (node (ref "RTC") (pin "2") (pinfunction "OSCO_2") (pintype "bidirectional"))
      (node (ref "U$14") (pin "P$1") (pinfunction "1_P$1") (pintype "passive"))
    )
    (net (code "69") (name "unconnected-(BRAINA-PA01-Pad2)") (class "Default")
      (node (ref "BRAIN") (pin "2") (pinfunction "PA01_2") (pintype "bidirectional"))
    )
    (net (code "70") (name "unconnected-(BRAINA-PA02-Pad9)") (class "Default")
      (node (ref "BRAIN") (pin "9") (pinfunction "PA02_9") (pintype "bidirectional"))
    )
    (net (code "71") (name "unconnected-(BRAINA-PA03-Pad10)") (class "Default")
      (node (ref "BRAIN") (pin "10") (pinfunction "PA03_10") (pintype "bidirectional"))
    )
    (net (code "72") (name "unconnected-(BRAINA-PA04-Pad21)") (class "Default")
      (node (ref "BRAIN") (pin "21") (pinfunction "PA04_21") (pintype "bidirectional"))
    )
    (net (code "73") (name "unconnected-(BRAINA-PA05-Pad22)") (class "Default")
      (node (ref "BRAIN") (pin "22") (pinfunction "PA05_22") (pintype "bidirectional"))
    )
    (net (code "74") (name "unconnected-(BRAINA-PA06-Pad23)") (class "Default")
      (node (ref "BRAIN") (pin "23") (pinfunction "PA06_23") (pintype "bidirectional"))
    )
    (net (code "75") (name "unconnected-(BRAINA-PA07-Pad24)") (class "Default")
      (node (ref "BRAIN") (pin "24") (pinfunction "PA07_24") (pintype "bidirectional"))
    )
    (net (code "76") (name "unconnected-(BRAINA-PA12-Pad60)") (class "Default")
      (node (ref "BRAIN") (pin "60") (pinfunction "PA12_60") (pintype "bidirectional"))
    )
    (net (code "77") (name "unconnected-(BRAINA-PA13-Pad61)") (class "Default")
      (node (ref "BRAIN") (pin "61") (pinfunction "PA13_61") (pintype "bidirectional"))
    )
    (net (code "78") (name "unconnected-(BRAINA-PA14-Pad62)") (class "Default")
      (node (ref "BRAIN") (pin "62") (pinfunction "PA14_62") (pintype "bidirectional"))
    )
    (net (code "79") (name "unconnected-(BRAINA-PA15-Pad63)") (class "Default")
      (node (ref "BRAIN") (pin "63") (pinfunction "PA15_63") (pintype "bidirectional"))
    )
    (net (code "80") (name "unconnected-(BRAINA-PA16-Pad66)") (class "Default")
      (node (ref "BRAIN") (pin "66") (pinfunction "PA16_66") (pintype "bidirectional"))
    )
    (net (code "81") (name "unconnected-(BRAINA-PA17-Pad67)") (class "Default")
      (node (ref "BRAIN") (pin "67") (pinfunction "PA17_67") (pintype "bidirectional"))
    )
    (net (code "82") (name "unconnected-(BRAINA-PA18-Pad68)") (class "Default")
      (node (ref "BRAIN") (pin "68") (pinfunction "PA18_68") (pintype "bidirectional"))
    )
    (net (code "83") (name "unconnected-(BRAINA-PA19-Pad69)") (class "Default")
      (node (ref "BRAIN") (pin "69") (pinfunction "PA19_69") (pintype "bidirectional"))
    )
    (net (code "84") (name "unconnected-(BRAINA-PA20-Pad88)") (class "Default")
      (node (ref "BRAIN") (pin "88") (pinfunction "PA20_88") (pintype "bidirectional"))
    )
    (net (code "85") (name "unconnected-(BRAINB-PB08-Pad19)") (class "Default")
      (node (ref "BRAIN") (pin "19") (pinfunction "PB08_19") (pintype "bidirectional"))
    )
    (net (code "86") (name "unconnected-(BRAINB-PB09-Pad20)") (class "Default")
      (node (ref "BRAIN") (pin "20") (pinfunction "PB09_20") (pintype "bidirectional"))
    )
    (net (code "87") (name "unconnected-(BRAINB-PB14-Pad43)") (class "Default")
      (node (ref "BRAIN") (pin "43") (pinfunction "PB14_43") (pintype "bidirectional"))
    )
    (net (code "88") (name "unconnected-(BRAINB-PB22-Pad98)") (class "Default")
      (node (ref "BRAIN") (pin "98") (pinfunction "PB22_98") (pintype "bidirectional"))
    )
    (net (code "89") (name "unconnected-(BRAINB-PB23-Pad99)") (class "Default")
      (node (ref "BRAIN") (pin "99") (pinfunction "PB23_99") (pintype "bidirectional"))
    )
    (net (code "90") (name "unconnected-(BRAINB-PB28-Pad104)") (class "Default")
      (node (ref "BRAIN") (pin "104") (pinfunction "PB28_104") (pintype "bidirectional"))
    )
    (net (code "91") (name "unconnected-(BRAINB-PB30-Pad121)") (class "Default")
      (node (ref "BRAIN") (pin "121") (pinfunction "PB30_121") (pintype "bidirectional"))
    )
    (net (code "92") (name "unconnected-(BRAINB-PB31-Pad122)") (class "Default")
      (node (ref "BRAIN") (pin "122") (pinfunction "PB31_122") (pintype "bidirectional"))
    )
    (net (code "93") (name "unconnected-(BRAINC-PC00-Pad3)") (class "Default")
      (node (ref "BRAIN") (pin "3") (pinfunction "PC00_3") (pintype "bidirectional"))
    )
    (net (code "94") (name "unconnected-(BRAINC-PC01-Pad4)") (class "Default")
      (node (ref "BRAIN") (pin "4") (pinfunction "PC01_4") (pintype "bidirectional"))
    )
    (net (code "95") (name "unconnected-(BRAINC-PC02-Pad7)") (class "Default")
      (node (ref "BRAIN") (pin "7") (pinfunction "PC02_7") (pintype "bidirectional"))
    )
    (net (code "96") (name "unconnected-(BRAINC-PC03-Pad8)") (class "Default")
      (node (ref "BRAIN") (pin "8") (pinfunction "PC03_8") (pintype "bidirectional"))
    )
    (net (code "97") (name "unconnected-(BRAINC-PC04-Pad27)") (class "Default")
      (node (ref "BRAIN") (pin "27") (pinfunction "PC04_27") (pintype "bidirectional"))
    )
    (net (code "98") (name "unconnected-(BRAINC-PC05-Pad28)") (class "Default")
      (node (ref "BRAIN") (pin "28") (pinfunction "PC05_28") (pintype "bidirectional"))
    )
    (net (code "99") (name "unconnected-(BRAINC-PC06-Pad29)") (class "Default")
      (node (ref "BRAIN") (pin "29") (pinfunction "PC06_29") (pintype "bidirectional"))
    )
    (net (code "100") (name "unconnected-(BRAINC-PC07-Pad30)") (class "Default")
      (node (ref "BRAIN") (pin "30") (pinfunction "PC07_30") (pintype "bidirectional"))
    )
    (net (code "101") (name "unconnected-(BRAINC-PC10-Pad52)") (class "Default")
      (node (ref "BRAIN") (pin "52") (pinfunction "PC10_52") (pintype "bidirectional"))
    )
    (net (code "102") (name "unconnected-(BRAINC-PC15-Pad59)") (class "Default")
      (node (ref "BRAIN") (pin "59") (pinfunction "PC15_59") (pintype "bidirectional"))
    )
    (net (code "103") (name "unconnected-(BRAINC-PC18-Pad72)") (class "Default")
      (node (ref "BRAIN") (pin "72") (pinfunction "PC18_72") (pintype "bidirectional"))
    )
    (net (code "104") (name "unconnected-(BRAINC-PC19-Pad73)") (class "Default")
      (node (ref "BRAIN") (pin "73") (pinfunction "PC19_73") (pintype "bidirectional"))
    )
    (net (code "105") (name "unconnected-(BRAINC-PC20-Pad74)") (class "Default")
      (node (ref "BRAIN") (pin "74") (pinfunction "PC20_74") (pintype "bidirectional"))
    )
    (net (code "106") (name "unconnected-(BRAINC-PC21-Pad75)") (class "Default")
      (node (ref "BRAIN") (pin "75") (pinfunction "PC21_75") (pintype "bidirectional"))
    )
    (net (code "107") (name "unconnected-(BRAIND-PD00-Pad13)") (class "Default")
      (node (ref "BRAIN") (pin "13") (pinfunction "PD00_13") (pintype "bidirectional"))
    )
    (net (code "108") (name "unconnected-(BRAIND-PD01-Pad16)") (class "Default")
      (node (ref "BRAIN") (pin "16") (pinfunction "PD01_16") (pintype "bidirectional"))
    )
    (net (code "109") (name "unconnected-(BRAIND-PD10-Pad49)") (class "Default")
      (node (ref "BRAIN") (pin "49") (pinfunction "PD10_49") (pintype "bidirectional"))
    )
    (net (code "110") (name "unconnected-(BRAIND-PD12-Pad51)") (class "Default")
      (node (ref "BRAIN") (pin "51") (pinfunction "PD12_51") (pintype "bidirectional"))
    )
    (net (code "111") (name "unconnected-(BRAIND-PD20-Pad80)") (class "Default")
      (node (ref "BRAIN") (pin "80") (pinfunction "PD20_80") (pintype "bidirectional"))
    )
    (net (code "112") (name "unconnected-(BRAIND-PD21-Pad81)") (class "Default")
      (node (ref "BRAIN") (pin "81") (pinfunction "PD21_81") (pintype "bidirectional"))
    )
    (net (code "113") (name "unconnected-(BRAINE-VSW-Pad117)") (class "Default")
      (node (ref "BRAIN") (pin "117") (pinfunction "VSW_117") (pintype "bidirectional"))
    )
    (net (code "114") (name "unconnected-(RTC-TS(CLK{slash}INTB)-Pad4)") (class "Default")
      (node (ref "RTC") (pin "4") (pinfunction "TS(CLK/INTB)_4") (pintype "bidirectional"))
    )
    (net (code "115") (name "unconnected-(RTC-~{INTA(CLK})-Pad9)") (class "Default")
      (node (ref "RTC") (pin "9") (pinfunction "~{INTA(CLK})_9") (pintype "bidirectional"))
    )
    (net (code "116") (name "unconnected-(SD-PadDAT1)") (class "Default")
      (node (ref "SD") (pin "DAT1") (pinfunction "DAT1_DAT1") (pintype "bidirectional"))
    )
    (net (code "117") (name "unconnected-(SD-PadDAT2)") (class "Default")
      (node (ref "SD") (pin "DAT2") (pinfunction "DAT2_DAT2") (pintype "bidirectional"))
    )
    (net (code "118") (name "unconnected-(SD-PadPAD1)") (class "Default")
      (node (ref "SD") (pin "PAD1") (pinfunction "PAD1_PAD1") (pintype "bidirectional"))
    )
    (net (code "119") (name "unconnected-(SD-PadPAD2)") (class "Default")
      (node (ref "SD") (pin "PAD2") (pinfunction "PAD2_PAD2") (pintype "bidirectional"))
    )
    (net (code "120") (name "unconnected-(SD-PadPAD3)") (class "Default")
      (node (ref "SD") (pin "PAD3") (pinfunction "PAD3_PAD3") (pintype "bidirectional"))
    )
    (net (code "121") (name "unconnected-(SD-PadPAD4)") (class "Default")
      (node (ref "SD") (pin "PAD4") (pinfunction "PAD4_PAD4") (pintype "bidirectional"))
    )
    (net (code "122") (name "unconnected-(SD-PadPAD5)") (class "Default")
      (node (ref "SD") (pin "PAD5") (pinfunction "PAD5_PAD5") (pintype "bidirectional"))
    )
    (net (code "123") (name "unconnected-(SD-PadPAD6)") (class "Default")
      (node (ref "SD") (pin "PAD6") (pinfunction "PAD6_PAD6") (pintype "bidirectional"))
    )
    (net (code "124") (name "unconnected-(U1-~{HOLD}{slash}SO3-PadP$7)") (class "Default")
      (node (ref "U1") (pin "P$7") (pinfunction "~{HOLD}/SO3_P$7") (pintype "bidirectional"))
    )
    (net (code "125") (name "unconnected-(U1-~{WP}{slash}SO2-PadP$3)") (class "Default")
      (node (ref "U1") (pin "P$3") (pinfunction "~{WP}/SO2_P$3") (pintype "bidirectional"))
    )
    (net (code "126") (name "unconnected-(U2-~{HOLD}{slash}SO3-PadP$7)") (class "Default")
      (node (ref "U2") (pin "P$7") (pinfunction "~{HOLD}/SO3_P$7") (pintype "bidirectional"))
    )
    (net (code "127") (name "unconnected-(U2-~{WP}{slash}SO2-PadP$3)") (class "Default")
      (node (ref "U2") (pin "P$3") (pinfunction "~{WP}/SO2_P$3") (pintype "bidirectional"))
    )
    (net (code "128") (name "unconnected-(U3-~{HOLD}{slash}SO3-PadP$7)") (class "Default")
      (node (ref "U3") (pin "P$7") (pinfunction "~{HOLD}/SO3_P$7") (pintype "bidirectional"))
    )
    (net (code "129") (name "unconnected-(U3-~{WP}{slash}SO2-PadP$3)") (class "Default")
      (node (ref "U3") (pin "P$3") (pinfunction "~{WP}/SO2_P$3") (pintype "bidirectional"))
    )
    (net (code "130") (name "unconnected-(U4-~{HOLD}{slash}SO3-PadP$7)") (class "Default")
      (node (ref "U4") (pin "P$7") (pinfunction "~{HOLD}/SO3_P$7") (pintype "bidirectional"))
    )
    (net (code "131") (name "unconnected-(U4-~{WP}{slash}SO2-PadP$3)") (class "Default")
      (node (ref "U4") (pin "P$3") (pinfunction "~{WP}/SO2_P$3") (pintype "bidirectional"))
    )
    (net (code "132") (name "unconnected-(USB-PadPAD1)") (class "Default")
      (node (ref "USB") (pin "PAD1") (pinfunction "PAD1_PAD1") (pintype "bidirectional"))
    )
    (net (code "133") (name "unconnected-(USB-PadPAD2)") (class "Default")
      (node (ref "USB") (pin "PAD2") (pinfunction "PAD2_PAD2") (pintype "bidirectional"))
    )
    (net (code "134") (name "unconnected-(USB-PadPAD3)") (class "Default")
      (node (ref "USB") (pin "PAD3") (pinfunction "PAD3_PAD3") (pintype "bidirectional"))
    )
    (net (code "135") (name "unconnected-(USB-PadPAD4)") (class "Default")
      (node (ref "USB") (pin "PAD4") (pinfunction "PAD4_PAD4") (pintype "bidirectional"))
    )
    (net (code "136") (name "unconnected-(USB-PadPAD5)") (class "Default")
      (node (ref "USB") (pin "PAD5") (pinfunction "PAD5_PAD5") (pintype "bidirectional"))
    )
    (net (code "137") (name "unconnected-(USB-PadPAD6)") (class "Default")
      (node (ref "USB") (pin "PAD6") (pinfunction "PAD6_PAD6") (pintype "bidirectional"))
    )
  )
)
